# WiFi_Board.net
KiCad netlist of a schematic drawn in EAGLE
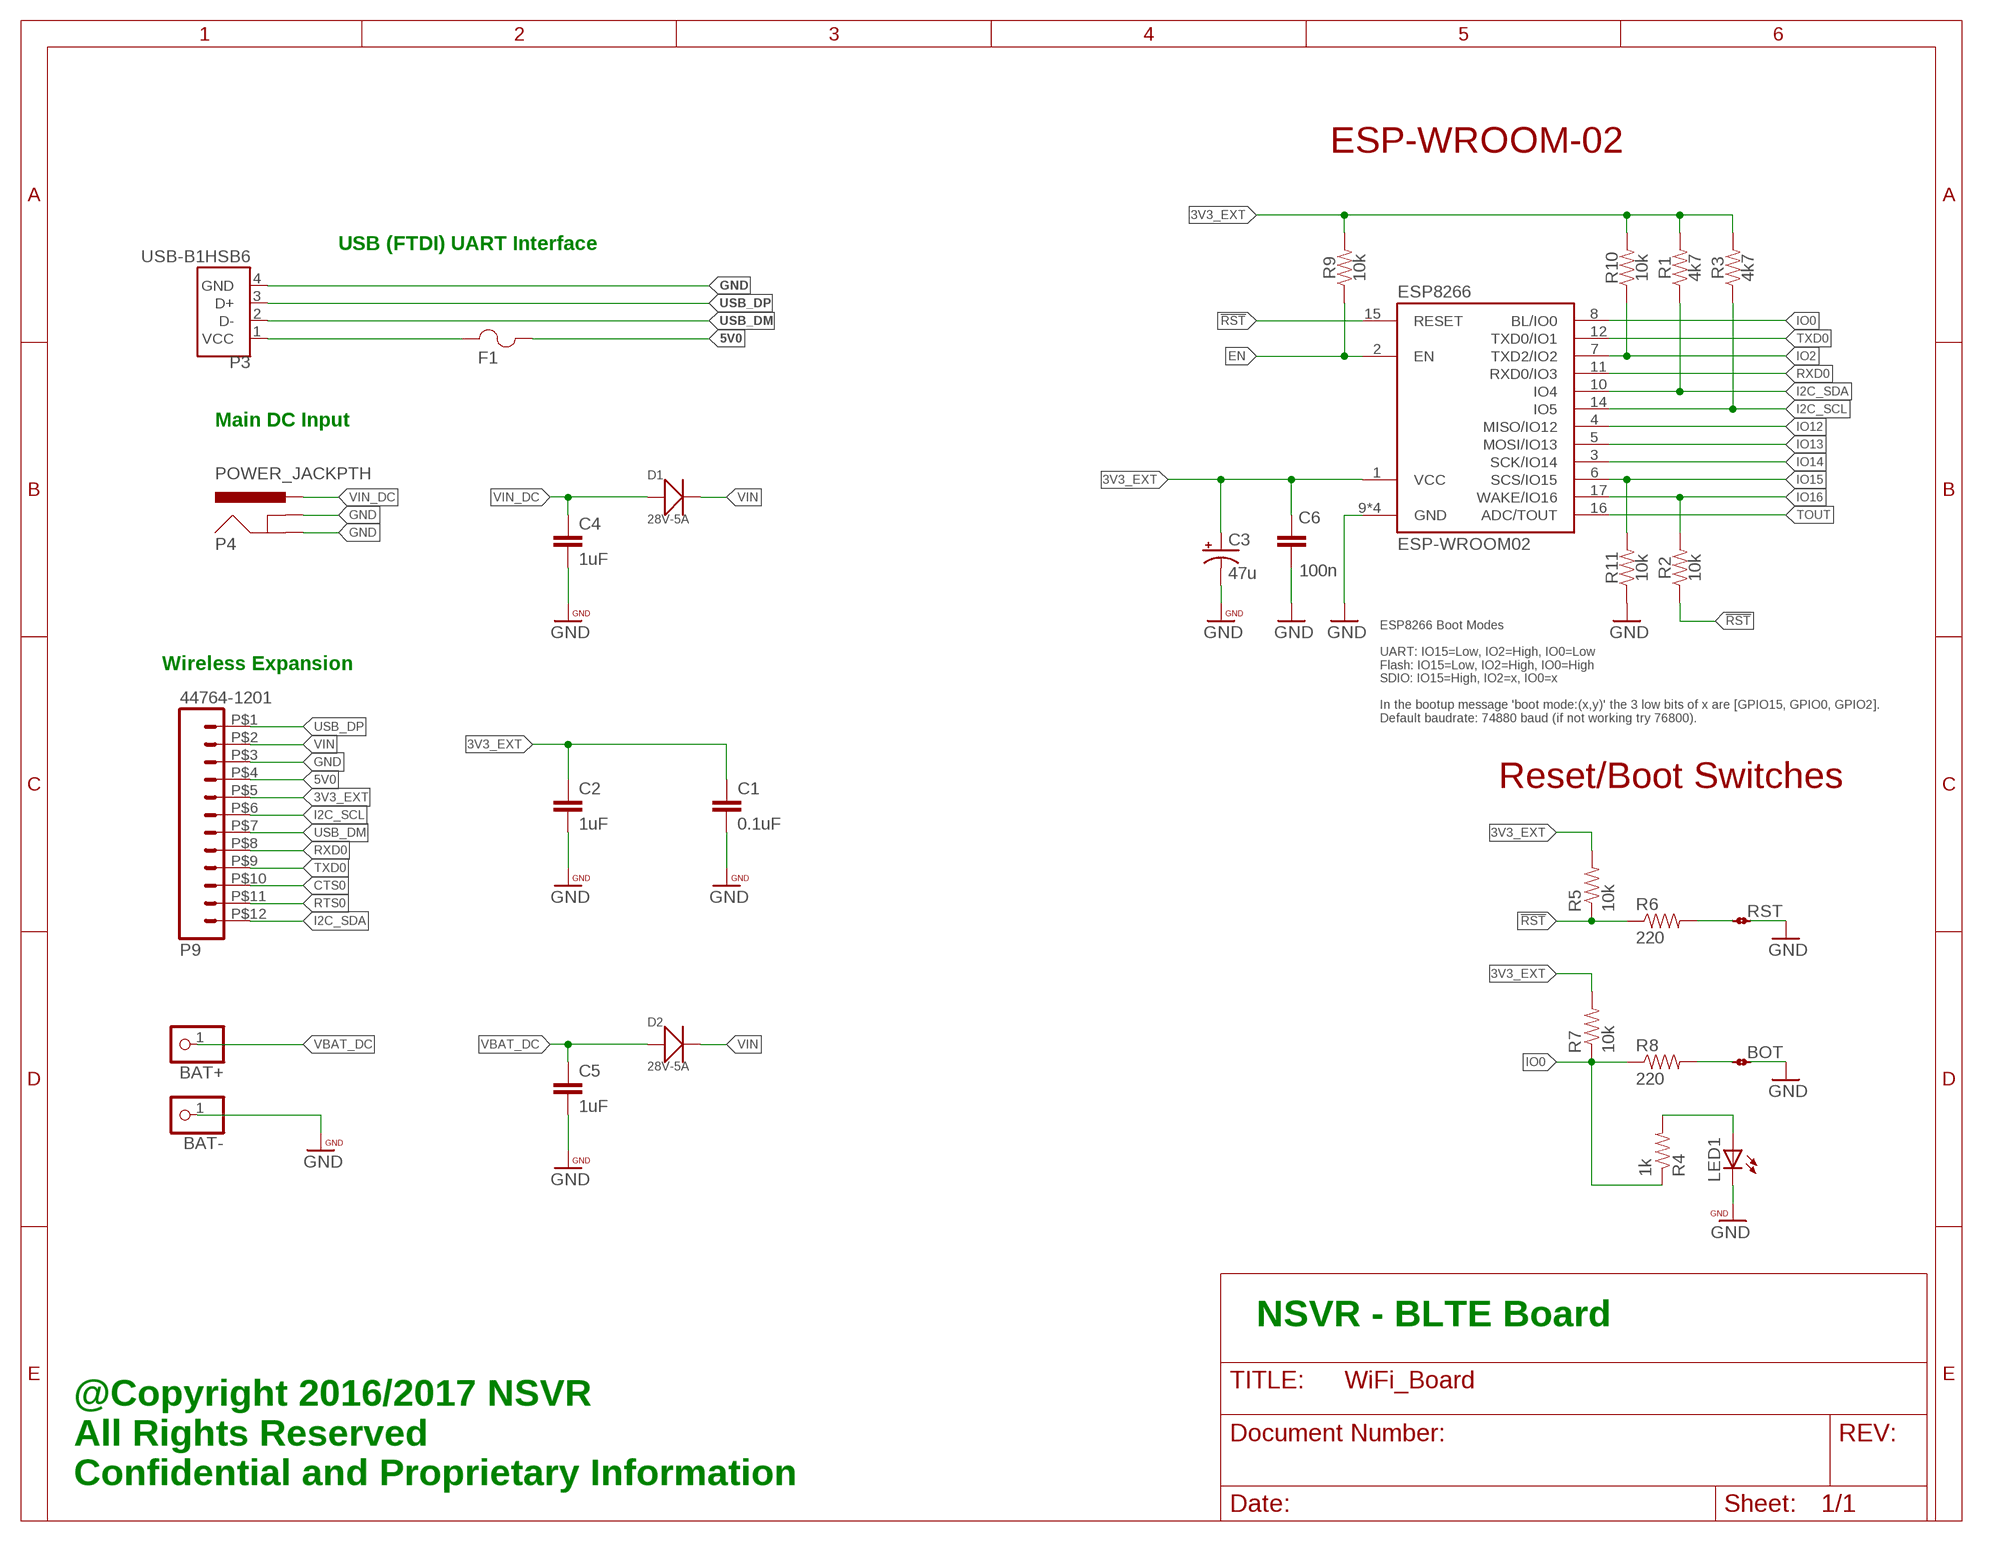
[diagram p0: schematic, sheet 1]

(export (version "E")
  (design (tool "Eeschema 10.0.6"))
  (components
    (comp (ref "BAT+")
      (value "WPAD-1-PTH")
      (footprint "eagle-import:WPAD-1-PTH-2.54")
      (libsource (lib "eagle-import") (part "WPAD-1-PTH"))
    )
    (comp (ref "BAT-")
      (value "WPAD-1-PTH")
      (footprint "eagle-import:WPAD-1-PTH-2.54")
      (libsource (lib "eagle-import") (part "WPAD-1-PTH"))
    )
    (comp (ref "BOT")
      (value "JMP-2-NO-PTH")
      (footprint "eagle-import:JMP-2-NO-PTH-2.54")
      (libsource (lib "eagle-import") (part "JMP-2-NO-PTH"))
    )
    (comp (ref "C1")
      (value "0.1uF")
      (footprint "eagle-import:0402-CAP")
      (libsource (lib "eagle-import") (part "CAP0402-CAP"))
    )
    (comp (ref "C2")
      (value "1uF")
      (footprint "eagle-import:0402-CAP")
      (libsource (lib "eagle-import") (part "CAP0402-CAP"))
    )
    (comp (ref "C3")
      (value "47u")
      (footprint "eagle-import:PANASONIC_D")
      (libsource (lib "eagle-import") (part "CAP_POLD"))
    )
    (comp (ref "C4")
      (value "1uF")
      (footprint "eagle-import:0402-CAP")
      (libsource (lib "eagle-import") (part "CAP0402-CAP"))
    )
    (comp (ref "C5")
      (value "1uF")
      (footprint "eagle-import:0402-CAP")
      (libsource (lib "eagle-import") (part "CAP0402-CAP"))
    )
    (comp (ref "C6")
      (value "100n")
      (footprint "eagle-import:0402-CAP")
      (libsource (lib "eagle-import") (part "CAP0402-CAP"))
    )
    (comp (ref "D1")
      (value "28V-5A")
      (footprint "eagle-import:DO-214AA")
      (fields (field (name "MPN") "SS54B"))
      (libsource (lib "eagle-import") (part "SMD-DIODE-SCHOTTKY-28V-5A(DO-214AA)"))
    )
    (comp (ref "D2")
      (value "28V-5A")
      (footprint "eagle-import:DO-214AA")
      (fields (field (name "MPN") "SS54B"))
      (libsource (lib "eagle-import") (part "SMD-DIODE-SCHOTTKY-28V-5A(DO-214AA)"))
    )
    (comp (ref "ESP8266")
      (value "ESP-WROOM02")
      (footprint "eagle-import:ESP-WROOM02")
      (libsource (lib "eagle-import") (part "ESP-WROOM02"))
    )
    (comp (ref "F1")
      (value "1206L050YR")
      (footprint "eagle-import:1206LSERIES")
      (fields (field (name "COPYRIGHT") "Copyright C 2015 Accelerated Designs. All rights reserved"))
      (libsource (lib "eagle-import") (part "1206L050YR"))
    )
    (comp (ref "LED1")
      (value "LEDCHIP-LED0603")
      (footprint "eagle-import:CHIP-LED0603")
      (libsource (lib "eagle-import") (part "LEDCHIP-LED0603"))
    )
    (comp (ref "P3")
      (value "USB-B1HSB6")
      (footprint "eagle-import:OST_USB-B1HSB6")
      (fields (field (name "MF") "On Shore Technology"))
      (libsource (lib "eagle-import") (part "USB-B1HSB6"))
    )
    (comp (ref "P4")
      (value "POWER_JACKPTH")
      (footprint "eagle-import:POWER_JACK_PTH")
      (libsource (lib "eagle-import") (part "POWER_JACKPTH"))
    )
    (comp (ref "P9")
      (value "44764-1201")
      (footprint "eagle-import:44764-1201")
      (libsource (lib "eagle-import") (part "44764-1201"))
    )
    (comp (ref "R1")
      (value "4k7")
      (footprint "eagle-import:EIA-0402")
      (libsource (lib "eagle-import") (part "RESISTOR0402-TYP"))
    )
    (comp (ref "R2")
      (value "10k")
      (footprint "eagle-import:EIA-0402")
      (libsource (lib "eagle-import") (part "RESISTOR0402-TYP"))
    )
    (comp (ref "R3")
      (value "4k7")
      (footprint "eagle-import:EIA-0402")
      (libsource (lib "eagle-import") (part "RESISTOR0402-TYP"))
    )
    (comp (ref "R4")
      (value "1k")
      (footprint "eagle-import:EIA-0402")
      (libsource (lib "eagle-import") (part "RESISTOR0402-TYP"))
    )
    (comp (ref "R5")
      (value "10k")
      (footprint "eagle-import:EIA-0402")
      (libsource (lib "eagle-import") (part "RESISTOR0402-TYP"))
    )
    (comp (ref "R6")
      (value "220")
      (footprint "eagle-import:EIA-0402")
      (libsource (lib "eagle-import") (part "RESISTOR0402-TYP"))
    )
    (comp (ref "R7")
      (value "10k")
      (footprint "eagle-import:EIA-0402")
      (libsource (lib "eagle-import") (part "RESISTOR0402-TYP"))
    )
    (comp (ref "R8")
      (value "220")
      (footprint "eagle-import:EIA-0402")
      (libsource (lib "eagle-import") (part "RESISTOR0402-TYP"))
    )
    (comp (ref "R9")
      (value "10k")
      (footprint "eagle-import:EIA-0402")
      (libsource (lib "eagle-import") (part "RESISTOR0402-TYP"))
    )
    (comp (ref "R10")
      (value "10k")
      (footprint "eagle-import:EIA-0402")
      (libsource (lib "eagle-import") (part "RESISTOR0402-TYP"))
    )
    (comp (ref "R11")
      (value "10k")
      (footprint "eagle-import:EIA-0402")
      (libsource (lib "eagle-import") (part "RESISTOR0402-TYP"))
    )
    (comp (ref "RST")
      (value "JMP-2-NO-PTH")
      (footprint "eagle-import:JMP-2-NO-PTH-2.54")
      (libsource (lib "eagle-import") (part "JMP-2-NO-PTH"))
    )
  )
  (nets
    (net (code "1") (name "/~{RST}") (class "Default")
      (node (ref "ESP8266") (pin "15") (pinfunction "RESET_15") (pintype "bidirectional"))
      (node (ref "R2") (pin "1") (pinfunction "1_1") (pintype "passive"))
      (node (ref "R5") (pin "1") (pinfunction "1_1") (pintype "passive"))
      (node (ref "R6") (pin "1") (pinfunction "1_1") (pintype "passive"))
    )
    (net (code "2") (name "3V3_EXT") (class "Default")
      (node (ref "C1") (pin "1") (pinfunction "1_1") (pintype "passive"))
      (node (ref "C2") (pin "1") (pinfunction "1_1") (pintype "passive"))
      (node (ref "C3") (pin "+") (pinfunction "+_+") (pintype "passive"))
      (node (ref "C6") (pin "2") (pinfunction "2_2") (pintype "passive"))
      (node (ref "ESP8266") (pin "1") (pinfunction "VCC_1") (pintype "power_in"))
      (node (ref "P9") (pin "P$5") (pinfunction "5_P$5") (pintype "passive"))
      (node (ref "R1") (pin "2") (pinfunction "2_2") (pintype "passive"))
      (node (ref "R10") (pin "2") (pinfunction "2_2") (pintype "passive"))
      (node (ref "R3") (pin "2") (pinfunction "2_2") (pintype "passive"))
      (node (ref "R5") (pin "2") (pinfunction "2_2") (pintype "passive"))
      (node (ref "R7") (pin "2") (pinfunction "2_2") (pintype "passive"))
      (node (ref "R9") (pin "2") (pinfunction "2_2") (pintype "passive"))
    )
    (net (code "3") (name "5V0") (class "Default")
      (node (ref "F1") (pin "2") (pinfunction "2_2") (pintype "passive"))
      (node (ref "P9") (pin "P$4") (pinfunction "4_P$4") (pintype "passive"))
    )
    (net (code "4") (name "CTS0") (class "Default")
      (node (ref "P9") (pin "P$10") (pinfunction "10_P$10") (pintype "passive"))
    )
    (net (code "5") (name "EN") (class "Default")
      (node (ref "ESP8266") (pin "2") (pinfunction "EN_2") (pintype "bidirectional"))
      (node (ref "R9") (pin "1") (pinfunction "1_1") (pintype "passive"))
    )
    (net (code "6") (name "GND") (class "Default")
      (node (ref "BAT-") (pin "1") (pinfunction "1_1") (pintype "passive"))
      (node (ref "BOT") (pin "2") (pinfunction "2_2") (pintype "passive"))
      (node (ref "C1") (pin "2") (pinfunction "2_2") (pintype "passive"))
      (node (ref "C2") (pin "2") (pinfunction "2_2") (pintype "passive"))
      (node (ref "C3") (pin "-") (pinfunction "-_-") (pintype "passive"))
      (node (ref "C4") (pin "2") (pinfunction "2_2") (pintype "passive"))
      (node (ref "C5") (pin "2") (pinfunction "2_2") (pintype "passive"))
      (node (ref "C6") (pin "1") (pinfunction "1_1") (pintype "passive"))
      (node (ref "ESP8266") (pin "13") (pinfunction "GND_13") (pintype "power_in"))
      (node (ref "ESP8266") (pin "18") (pinfunction "GND_18") (pintype "power_in"))
      (node (ref "ESP8266") (pin "9") (pinfunction "GND_9") (pintype "power_in"))
      (node (ref "ESP8266") (pin "TP") (pinfunction "GND_TP") (pintype "power_in"))
      (node (ref "LED1") (pin "C") (pinfunction "C_C") (pintype "passive"))
      (node (ref "P3") (pin "4") (pinfunction "GND_4") (pintype "power_in"))
      (node (ref "P4") (pin "GND") (pinfunction "GND_GND") (pintype "bidirectional"))
      (node (ref "P4") (pin "GNDBREAK") (pinfunction "GNDBREAK_GNDBREAK") (pintype "bidirectional"))
      (node (ref "P9") (pin "P$3") (pinfunction "3_P$3") (pintype "passive"))
      (node (ref "R11") (pin "1") (pinfunction "1_1") (pintype "passive"))
      (node (ref "RST") (pin "2") (pinfunction "2_2") (pintype "passive"))
    )
    (net (code "7") (name "I2C_SCL") (class "Default")
      (node (ref "ESP8266") (pin "14") (pinfunction "IO5_14") (pintype "bidirectional"))
      (node (ref "P9") (pin "P$6") (pinfunction "6_P$6") (pintype "passive"))
      (node (ref "R3") (pin "1") (pinfunction "1_1") (pintype "passive"))
    )
    (net (code "8") (name "I2C_SDA") (class "Default")
      (node (ref "ESP8266") (pin "10") (pinfunction "IO4_10") (pintype "bidirectional"))
      (node (ref "P9") (pin "P$12") (pinfunction "12_P$12") (pintype "passive"))
      (node (ref "R1") (pin "1") (pinfunction "1_1") (pintype "passive"))
    )
    (net (code "9") (name "IO0") (class "Default")
      (node (ref "ESP8266") (pin "8") (pinfunction "BL/IO0_8") (pintype "bidirectional"))
      (node (ref "R4") (pin "1") (pinfunction "1_1") (pintype "passive"))
      (node (ref "R7") (pin "1") (pinfunction "1_1") (pintype "passive"))
      (node (ref "R8") (pin "1") (pinfunction "1_1") (pintype "passive"))
    )
    (net (code "10") (name "IO2") (class "Default")
      (node (ref "ESP8266") (pin "7") (pinfunction "TXD2/IO2_7") (pintype "bidirectional"))
      (node (ref "R10") (pin "1") (pinfunction "1_1") (pintype "passive"))
    )
    (net (code "11") (name "IO12") (class "Default")
      (node (ref "ESP8266") (pin "4") (pinfunction "MISO/IO12_4") (pintype "bidirectional"))
    )
    (net (code "12") (name "IO13") (class "Default")
      (node (ref "ESP8266") (pin "5") (pinfunction "MOSI/IO13_5") (pintype "bidirectional"))
    )
    (net (code "13") (name "IO14") (class "Default")
      (node (ref "ESP8266") (pin "3") (pinfunction "SCK/IO14_3") (pintype "bidirectional"))
    )
    (net (code "14") (name "IO15") (class "Default")
      (node (ref "ESP8266") (pin "6") (pinfunction "SCS/IO15_6") (pintype "bidirectional"))
      (node (ref "R11") (pin "2") (pinfunction "2_2") (pintype "passive"))
    )
    (net (code "15") (name "IO16") (class "Default")
      (node (ref "ESP8266") (pin "17") (pinfunction "WAKE/IO16_17") (pintype "bidirectional"))
      (node (ref "R2") (pin "2") (pinfunction "2_2") (pintype "passive"))
    )
    (net (code "16") (name "Net-(BOT-Pad1)") (class "Default")
      (node (ref "BOT") (pin "1") (pinfunction "1_1") (pintype "passive"))
      (node (ref "R8") (pin "2") (pinfunction "2_2") (pintype "passive"))
    )
    (net (code "17") (name "Net-(LED1-PadA)") (class "Default")
      (node (ref "LED1") (pin "A") (pinfunction "A_A") (pintype "passive"))
      (node (ref "R4") (pin "2") (pinfunction "2_2") (pintype "passive"))
    )
    (net (code "18") (name "Net-(P3-VCC)") (class "Default")
      (node (ref "F1") (pin "1") (pinfunction "1_1") (pintype "passive"))
      (node (ref "P3") (pin "1") (pinfunction "VCC_1") (pintype "power_in"))
    )
    (net (code "19") (name "Net-(R6-Pad2)") (class "Default")
      (node (ref "R6") (pin "2") (pinfunction "2_2") (pintype "passive"))
      (node (ref "RST") (pin "1") (pinfunction "1_1") (pintype "passive"))
    )
    (net (code "20") (name "RTS0") (class "Default")
      (node (ref "P9") (pin "P$11") (pinfunction "11_P$11") (pintype "passive"))
    )
    (net (code "21") (name "RXD0") (class "Default")
      (node (ref "ESP8266") (pin "11") (pinfunction "RXD0/IO3_11") (pintype "bidirectional"))
      (node (ref "P9") (pin "P$8") (pinfunction "8_P$8") (pintype "passive"))
    )
    (net (code "22") (name "TOUT") (class "Default")
      (node (ref "ESP8266") (pin "16") (pinfunction "ADC/TOUT_16") (pintype "bidirectional"))
    )
    (net (code "23") (name "TXD0") (class "Default")
      (node (ref "ESP8266") (pin "12") (pinfunction "TXD0/IO1_12") (pintype "bidirectional"))
      (node (ref "P9") (pin "P$9") (pinfunction "9_P$9") (pintype "passive"))
    )
    (net (code "24") (name "USB_DM") (class "Default")
      (node (ref "P3") (pin "2") (pinfunction "D-_2") (pintype "bidirectional"))
      (node (ref "P9") (pin "P$7") (pinfunction "7_P$7") (pintype "passive"))
    )
    (net (code "25") (name "USB_DP") (class "Default")
      (node (ref "P3") (pin "3") (pinfunction "D+_3") (pintype "bidirectional"))
      (node (ref "P9") (pin "P$1") (pinfunction "1_P$1") (pintype "passive"))
    )
    (net (code "26") (name "VBAT_DC") (class "Default")
      (node (ref "BAT+") (pin "1") (pinfunction "1_1") (pintype "passive"))
      (node (ref "C5") (pin "1") (pinfunction "1_1") (pintype "passive"))
      (node (ref "D2") (pin "+") (pinfunction "+_+") (pintype "passive"))
    )
    (net (code "27") (name "VIN") (class "Default")
      (node (ref "D1") (pin "-") (pinfunction "-_-") (pintype "passive"))
      (node (ref "D2") (pin "-") (pinfunction "-_-") (pintype "passive"))
      (node (ref "P9") (pin "P$2") (pinfunction "2_P$2") (pintype "passive"))
    )
    (net (code "28") (name "VIN_DC") (class "Default")
      (node (ref "C4") (pin "1") (pinfunction "1_1") (pintype "passive"))
      (node (ref "D1") (pin "+") (pinfunction "+_+") (pintype "passive"))
      (node (ref "P4") (pin "PWR") (pinfunction "PWR_PWR") (pintype "bidirectional"))
    )
  )
)
